# WIFI_ESP8285_ESP8266.net
KiCad netlist of a schematic drawn in Altium Designer
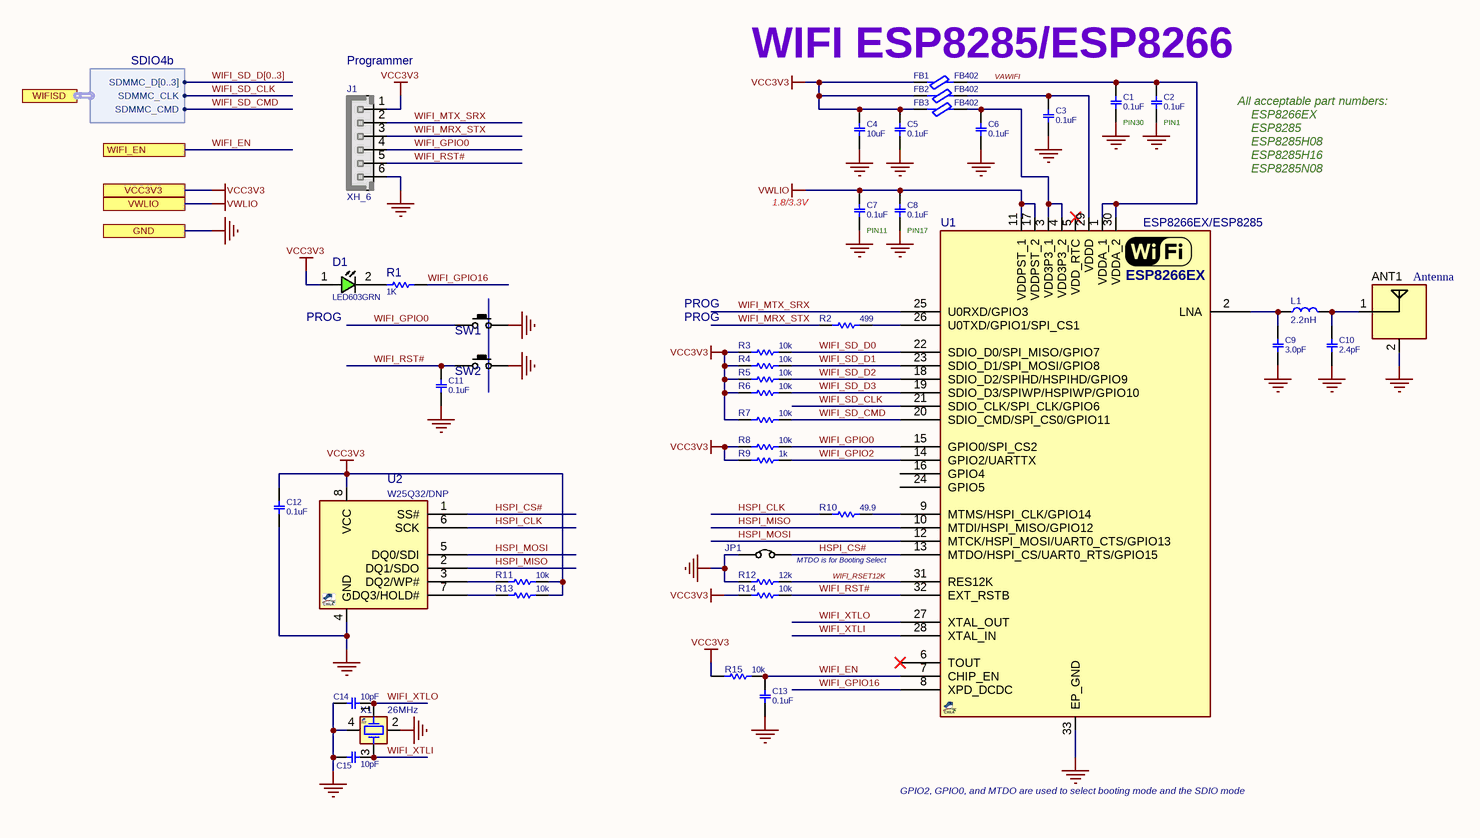
[diagram p0: WIFI_ESP8285_ESP8266.SchDoc]

(export (version "E")
  (design (tool "Eeschema 10.0.6"))
  (components
    (comp (ref "ANT1")
      (value "Antenna")
      (footprint "ANT_PCB_2P4G_IFA")
      (description "Antenna,Microstrip, 2.4GHz")
      (fields (field (name "MANF") "MANF") (field (name "MANF_P#") "MANF_P#"))
      (libsource (lib "antenna") (part "ANT_PCB_2P4G_IFA"))
    )
    (comp (ref "C1")
      (value "0.1uF")
      (footprint "C0402")
      (description "CAP, MLCC")
      (libsource (lib "mlcc_smd_passive") (part "CAP_SMD_MLCC_100n50T"))
    )
    (comp (ref "C2")
      (value "0.1uF")
      (footprint "C0402")
      (description "CAP, MLCC")
      (libsource (lib "mlcc_smd_passive") (part "CAP_SMD_MLCC_100n50T"))
    )
    (comp (ref "C3")
      (value "0.1uF")
      (footprint "C0402")
      (description "CAP, MLCC")
      (libsource (lib "mlcc_smd_passive") (part "CAP_SMD_MLCC_100n50T"))
    )
    (comp (ref "C4")
      (value "10uF")
      (footprint "C0402")
      (description "CAP, MLCC")
      (libsource (lib "mlcc_smd_passive") (part "CAP_SMD_MLCC_100n50T"))
    )
    (comp (ref "C5")
      (value "0.1uF")
      (footprint "C0402")
      (description "CAP, MLCC")
      (libsource (lib "mlcc_smd_passive") (part "CAP_SMD_MLCC_100n50T"))
    )
    (comp (ref "C6")
      (value "0.1uF")
      (footprint "C0402")
      (description "CAP, MLCC")
      (libsource (lib "mlcc_smd_passive") (part "CAP_SMD_MLCC_100n50T"))
    )
    (comp (ref "C7")
      (value "0.1uF")
      (footprint "C0402")
      (description "CAP, MLCC")
      (libsource (lib "mlcc_smd_passive") (part "CAP_SMD_MLCC_100n50T"))
    )
    (comp (ref "C8")
      (value "0.1uF")
      (footprint "C0402")
      (description "CAP, MLCC")
      (libsource (lib "mlcc_smd_passive") (part "CAP_SMD_MLCC_100n50T"))
    )
    (comp (ref "C9")
      (value "3.0pF")
      (footprint "C0402")
      (description "CAP, MLCC")
      (libsource (lib "mlcc_smd_passive") (part "CAP_SMD_MLCC_100n50T"))
    )
    (comp (ref "C10")
      (value "2.4pF")
      (footprint "C0402")
      (description "CAP, MLCC")
      (libsource (lib "mlcc_smd_passive") (part "CAP_SMD_MLCC_100n50T"))
    )
    (comp (ref "C11")
      (value "0.1uF")
      (footprint "C0402")
      (description "CAP, 100nF, 6.3V, C0G,  0402")
      (fields (field (name "MANF_P#") "MANF_PART#") (field (name "MANF") "Murata"))
      (libsource (lib "espwroom2_wifi_module") (part "CAP_SMD_MLCC_1"))
    )
    (comp (ref "C12")
      (value "0.1uF")
      (footprint "C0402")
      (description "CAP, MLCC")
      (libsource (lib "mlcc_smd_passive") (part "CAP_SMD_MLCC_100n50T"))
    )
    (comp (ref "C13")
      (value "0.1uF")
      (footprint "C0402")
      (description "CAP, MLCC")
      (libsource (lib "mlcc_smd_passive") (part "CAP_SMD_MLCC_100n50T"))
    )
    (comp (ref "C14")
      (value "10pF")
      (footprint "C0402")
      (description "CAP, 100nF, 6.3V, C0G,  0402")
      (fields (field (name "MANF_P#") "MANF_PART#") (field (name "MANF") "Murata"))
      (libsource (lib "espwroom2_wifi_module") (part "CAP_SMD_MLCC_1"))
    )
    (comp (ref "C15")
      (value "10pF")
      (footprint "C0402")
      (description "CAP, 100nF, 6.3V, C0G,  0402")
      (fields (field (name "MANF_P#") "MANF_PART#") (field (name "MANF") "Murata"))
      (libsource (lib "espwroom2_wifi_module") (part "CAP_SMD_MLCC_1"))
    )
    (comp (ref "D1")
      (value "LED603GRN")
      (footprint "LED0603")
      (description "LED, SMD, 0603, GREEN")
      (fields (field (name "MANF") "Kingbright") (field (name "MANF_P#") "APT1608SGC"))
      (libsource (lib "led(diode)") (part "LED_SMD_0603_GRN"))
    )
    (comp (ref "FB1")
      (value "FB402")
      (footprint "L0402")
      (description "FERRITE_Bead, 0402, 0.5A, 200mOhm, 120@100MHz")
      (fields (field (name "MANF") "MURATA") (field (name "MANF_P#") "BLM15AG121SN1D"))
      (libsource (lib "emi_filter") (part "FBEAD_SMD_BLM15PD121"))
    )
    (comp (ref "FB2")
      (value "FB402")
      (footprint "L0402")
      (description "FERRITE_Bead, 0402, 0.5A, 200mOhm, 120@100MHz")
      (fields (field (name "MANF") "MURATA") (field (name "MANF_P#") "BLM15AG121SN1D"))
      (libsource (lib "emi_filter") (part "FBEAD_SMD_BLM15PD121"))
    )
    (comp (ref "FB3")
      (value "FB402")
      (footprint "L0402")
      (description "FERRITE_Bead, 0402, 0.5A, 200mOhm, 120@100MHz")
      (fields (field (name "MANF") "MURATA") (field (name "MANF_P#") "BLM15AG121SN1D"))
      (libsource (lib "emi_filter") (part "FBEAD_SMD_BLM15PD121"))
    )
    (comp (ref "J1")
      (value "XH_6")
      (footprint "XH_6")
      (description "JST-XH pitch: 2.5mm")
      (fields (field (name "MANF_P#") "JST-S6B-XHA") (field (name "MANF") "JST"))
      (libsource (lib "conn_wire2board") (part "XH_6"))
    )
    (comp (ref "JP1")
      (value "JMPHDR2PIN")
      (footprint "JP_2_BLK")
      (description "JUMPER, HEADER 2PIN")
      (fields (field (name "MANF") "MANF") (field (name "MANF_P#") "MANF_P#"))
      (libsource (lib "test-tp_jumper") (part "JUMPER_HDR_2P"))
    )
    (comp (ref "L1")
      (value "2.2nH")
      (footprint "L0402")
      (description "INDUCTOR, SMD")
      (libsource (lib "passive_smd") (part "IND_SMD"))
    )
    (comp (ref "R1")
      (value "1K")
      (footprint "R0402")
      (description "RESISTOR, SMD")
      (fields (field (name "MANF_P#") "RK73H1ETTP4701F") (field (name "MANF") "KOA SPEER"))
      (libsource (lib "espwroom2_wifi_module") (part "RES_SMD"))
    )
    (comp (ref "R2")
      (value "499")
      (footprint "R0402")
      (description "RESISTOR, SMD")
      (libsource (lib "passive_res_smd") (part "RES_SMD_10K_0402"))
    )
    (comp (ref "R3")
      (value "10k")
      (footprint "R0402")
      (description "RESISTOR, SMD")
      (libsource (lib "passive_res_smd") (part "RES_SMD_10K_0402"))
    )
    (comp (ref "R4")
      (value "10k")
      (footprint "R0402")
      (description "RESISTOR, SMD")
      (libsource (lib "passive_res_smd") (part "RES_SMD_10K_0402"))
    )
    (comp (ref "R5")
      (value "10k")
      (footprint "R0402")
      (description "RESISTOR, SMD")
      (libsource (lib "passive_res_smd") (part "RES_SMD_10K_0402"))
    )
    (comp (ref "R6")
      (value "10k")
      (footprint "R0402")
      (description "RESISTOR, SMD")
      (libsource (lib "passive_res_smd") (part "RES_SMD_10K_0402"))
    )
    (comp (ref "R7")
      (value "10k")
      (footprint "R0402")
      (description "RESISTOR, SMD")
      (libsource (lib "passive_res_smd") (part "RES_SMD_10K_0402"))
    )
    (comp (ref "R8")
      (value "10k")
      (footprint "R0402")
      (description "RESISTOR, SMD")
      (libsource (lib "passive_res_smd") (part "RES_SMD_10K_0402"))
    )
    (comp (ref "R9")
      (value "1k")
      (footprint "R0402")
      (description "RESISTOR, SMD")
      (libsource (lib "passive_res_smd") (part "RES_SMD_10K_0402"))
    )
    (comp (ref "R10")
      (value "49.9")
      (footprint "R0402")
      (description "RESISTOR, SMD")
      (libsource (lib "passive_res_smd") (part "RES_SMD_10K_0402"))
    )
    (comp (ref "R11")
      (value "10k")
      (footprint "R0402")
      (description "RESISTOR, SMD")
      (libsource (lib "passive_res_smd") (part "RES_SMD_10K_0402"))
    )
    (comp (ref "R12")
      (value "12k")
      (footprint "R0402")
      (description "RESISTOR, SMD")
      (libsource (lib "passive_res_smd") (part "RES_SMD_10K_0402"))
    )
    (comp (ref "R13")
      (value "10k")
      (footprint "R0402")
      (description "RESISTOR, SMD")
      (libsource (lib "passive_res_smd") (part "RES_SMD_10K_0402"))
    )
    (comp (ref "R14")
      (value "10k")
      (footprint "R0402")
      (description "RESISTOR, SMD")
      (libsource (lib "passive_res_smd") (part "RES_SMD_10K_0402"))
    )
    (comp (ref "R15")
      (value "10k")
      (footprint "R0402")
      (description "RESISTOR, SMD")
      (libsource (lib "passive_res_smd") (part "RES_SMD_10K_0402"))
    )
    (comp (ref "SW1")
      (value "PUSHBUTTON")
      (footprint "SWPBS_SPST_3X2X1")
      (description "SWITCH, PUSH BUTTON, TACTILE, SMD, SPST, 3X2.5X1.2mm")
      (fields (field (name "MANF") "OMRON") (field (name "MANF_P#") "B3U-1000P"))
      (libsource (lib "switch_tact_PUSHB") (part "SWPBS_SPST_3X2_B3U-1000P"))
    )
    (comp (ref "SW2")
      (value "PUSHBUTTON")
      (footprint "SWPBS_SPST_3X2X1")
      (description "SWITCH, PUSH BUTTON, TACTILE, SMD, SPST, 3X2.5X1.2mm")
      (fields (field (name "MANF") "OMRON") (field (name "MANF_P#") "B3U-1000P"))
      (libsource (lib "switch_tact_PUSHB") (part "SWPBS_SPST_3X2_B3U-1000P"))
    )
    (comp (ref "U1")
      (value "ESP8266EX/ESP8285")
      (footprint "QFN50_32T")
      (description "ESP8266EX, RF SoC")
      (fields (field (name "MANF") "Espressif Systems") (field (name "MANF_P#") "ESP8266EX"))
      (libsource (lib "wifi_ic") (part "ESP8266EX_QFN32"))
    )
    (comp (ref "U2")
      (value "W25Q32/DNP")
      (footprint "SO_8_W")
      (description "SPI FLASH Memory, 64Mb (8M x8), 104MHz")
      (fields (field (name "MANF") "WINBOND") (field (name "MANF_P#") "W25Q32JVSSIQ"))
      (libsource (lib "memory_flash_spi") (part "W25Q64FV_SO8W"))
    )
    (comp (ref "X1")
      (value "26MHz")
      (footprint "XTL_4_2016")
      (description "Crystal 26MHz")
      (fields (field (name "MANF") "MURATA") (field (name "MANF_P#") "XRCGB26M000F1H00R0"))
      (libsource (lib "crystal") (part "XTL_4_26MHz_2016"))
    )
  )
  (nets
    (net (code "2") (name "/HSPI_CLK") (class "Default")
      (node (ref "R10") (pin "1") (pinfunction "1_1") (pintype "passive"))
      (node (ref "U2") (pin "6") (pinfunction "SCK_6") (pintype "passive"))
    )
    (net (code "3") (name "/HSPI_CS#") (class "Default")
      (node (ref "JP1") (pin "2") (pinfunction "2_2") (pintype "passive"))
      (node (ref "U1") (pin "13") (pinfunction "MTDO/HSPI_CS/UART0_RTS/GPIO15_13") (pintype "passive"))
      (node (ref "U2") (pin "1") (pinfunction "SS#_1") (pintype "passive"))
    )
    (net (code "4") (name "/HSPI_MISO") (class "Default")
      (node (ref "U1") (pin "10") (pinfunction "MTDI/HSPI_MISO/GPIO12_10") (pintype "passive"))
      (node (ref "U2") (pin "2") (pinfunction "DQ1/SDO_2") (pintype "passive"))
    )
    (net (code "5") (name "/HSPI_MOSI") (class "Default")
      (node (ref "U1") (pin "12") (pinfunction "MTCK/HSPI_MOSI/UART0_CTS/GPIO13_12") (pintype "passive"))
      (node (ref "U2") (pin "5") (pinfunction "DQ0/SDI_5") (pintype "passive"))
    )
    (net (code "6") (name "/VAWIFI") (class "Default")
      (node (ref "C1") (pin "1") (pinfunction "1_1") (pintype "passive"))
      (node (ref "C2") (pin "1") (pinfunction "1_1") (pintype "passive"))
      (node (ref "FB1") (pin "2") (pinfunction "2_2") (pintype "passive"))
      (node (ref "U1") (pin "1") (pinfunction "VDDA_1_1") (pintype "passive"))
      (node (ref "U1") (pin "30") (pinfunction "VDDA_2_30") (pintype "passive"))
    )
    (net (code "8") (name "/WIFI_EN") (class "Default")
      (node (ref "C13") (pin "1") (pinfunction "1_1") (pintype "passive"))
      (node (ref "R15") (pin "2") (pinfunction "2_2") (pintype "passive"))
      (node (ref "U1") (pin "7") (pinfunction "CHIP_EN_7") (pintype "passive"))
    )
    (net (code "9") (name "/WIFI_GPIO0") (class "Default")
      (node (ref "J1") (pin "4") (pinfunction "4_4") (pintype "passive"))
      (node (ref "R8") (pin "2") (pinfunction "2_2") (pintype "passive"))
      (node (ref "SW1") (pin "1") (pinfunction "P1_1") (pintype "passive"))
      (node (ref "U1") (pin "15") (pinfunction "GPIO0/SPI_CS2_15") (pintype "passive"))
    )
    (net (code "10") (name "/WIFI_GPIO2") (class "Default")
      (node (ref "R9") (pin "2") (pinfunction "2_2") (pintype "passive"))
      (node (ref "U1") (pin "14") (pinfunction "GPIO2/UARTTX_14") (pintype "passive"))
    )
    (net (code "11") (name "/WIFI_GPIO16") (class "Default")
      (node (ref "R1") (pin "2") (pinfunction "2_2") (pintype "passive"))
      (node (ref "U1") (pin "8") (pinfunction "XPD_DCDC_8") (pintype "passive"))
    )
    (net (code "12") (name "/WIFI_MRX_STX") (class "Default")
      (node (ref "J1") (pin "3") (pinfunction "3_3") (pintype "passive"))
      (node (ref "R2") (pin "1") (pinfunction "1_1") (pintype "passive"))
    )
    (net (code "13") (name "/WIFI_MTX_SRX") (class "Default")
      (node (ref "J1") (pin "2") (pinfunction "2_2") (pintype "passive"))
      (node (ref "U1") (pin "25") (pinfunction "U0RXD/GPIO3_25") (pintype "passive"))
    )
    (net (code "14") (name "/WIFI_RSET12K") (class "Default")
      (node (ref "R12") (pin "2") (pinfunction "2_2") (pintype "passive"))
      (node (ref "U1") (pin "31") (pinfunction "RES12K_31") (pintype "passive"))
    )
    (net (code "15") (name "/WIFI_RST#") (class "Default")
      (node (ref "C11") (pin "2") (pinfunction "2_2") (pintype "passive"))
      (node (ref "J1") (pin "5") (pinfunction "5_5") (pintype "passive"))
      (node (ref "R14") (pin "2") (pinfunction "2_2") (pintype "passive"))
      (node (ref "SW2") (pin "1") (pinfunction "P1_1") (pintype "passive"))
      (node (ref "U1") (pin "32") (pinfunction "EXT_RSTB_32") (pintype "passive"))
    )
    (net (code "16") (name "/WIFI_SD_CLK") (class "Default")
      (node (ref "U1") (pin "21") (pinfunction "SDIO_CLK/SPI_CLK/GPIO6_21") (pintype "passive"))
    )
    (net (code "17") (name "/WIFI_SD_CMD") (class "Default")
      (node (ref "R7") (pin "2") (pinfunction "2_2") (pintype "passive"))
      (node (ref "U1") (pin "20") (pinfunction "SDIO_CMD/SPI_CS0/GPIO11_20") (pintype "passive"))
    )
    (net (code "18") (name "/WIFI_SD_D0") (class "Default")
      (node (ref "R3") (pin "2") (pinfunction "2_2") (pintype "passive"))
      (node (ref "U1") (pin "22") (pinfunction "SDIO_D0/SPI_MISO/GPIO7_22") (pintype "passive"))
    )
    (net (code "19") (name "/WIFI_SD_D1") (class "Default")
      (node (ref "R4") (pin "2") (pinfunction "2_2") (pintype "passive"))
      (node (ref "U1") (pin "23") (pinfunction "SDIO_D1/SPI_MOSI/GPIO8_23") (pintype "passive"))
    )
    (net (code "20") (name "/WIFI_SD_D2") (class "Default")
      (node (ref "R5") (pin "2") (pinfunction "2_2") (pintype "passive"))
      (node (ref "U1") (pin "18") (pinfunction "SDIO_D2/SPIHD/HSPIHD/GPIO9_18") (pintype "passive"))
    )
    (net (code "21") (name "/WIFI_SD_D3") (class "Default")
      (node (ref "R6") (pin "2") (pinfunction "2_2") (pintype "passive"))
      (node (ref "U1") (pin "19") (pinfunction "SDIO_D3/SPIWP/HSPIWP/GPIO10_19") (pintype "passive"))
    )
    (net (code "22") (name "/WIFI_XTLI") (class "Default")
      (node (ref "C15") (pin "2") (pinfunction "2_2") (pintype "passive"))
      (node (ref "U1") (pin "28") (pinfunction "XTAL_IN_28") (pintype "passive"))
      (node (ref "X1") (pin "3") (pinfunction "2_3") (pintype "passive"))
    )
    (net (code "23") (name "/WIFI_XTLO") (class "Default")
      (node (ref "C14") (pin "2") (pinfunction "2_2") (pintype "passive"))
      (node (ref "U1") (pin "27") (pinfunction "XTAL_OUT_27") (pintype "passive"))
      (node (ref "X1") (pin "1") (pinfunction "1_1") (pintype "passive"))
    )
    (net (code "25") (name "GND") (class "Default")
      (node (ref "ANT1") (pin "2") (pinfunction "RETURN_2") (pintype "passive"))
      (node (ref "C1") (pin "2") (pinfunction "2_2") (pintype "passive"))
      (node (ref "C10") (pin "1") (pinfunction "1_1") (pintype "passive"))
      (node (ref "C11") (pin "1") (pinfunction "1_1") (pintype "passive"))
      (node (ref "C12") (pin "2") (pinfunction "2_2") (pintype "passive"))
      (node (ref "C13") (pin "2") (pinfunction "2_2") (pintype "passive"))
      (node (ref "C14") (pin "1") (pinfunction "1_1") (pintype "passive"))
      (node (ref "C15") (pin "1") (pinfunction "1_1") (pintype "passive"))
      (node (ref "C2") (pin "2") (pinfunction "2_2") (pintype "passive"))
      (node (ref "C3") (pin "2") (pinfunction "2_2") (pintype "passive"))
      (node (ref "C4") (pin "1") (pinfunction "1_1") (pintype "passive"))
      (node (ref "C5") (pin "1") (pinfunction "1_1") (pintype "passive"))
      (node (ref "C6") (pin "2") (pinfunction "2_2") (pintype "passive"))
      (node (ref "C7") (pin "2") (pinfunction "2_2") (pintype "passive"))
      (node (ref "C8") (pin "2") (pinfunction "2_2") (pintype "passive"))
      (node (ref "C9") (pin "1") (pinfunction "1_1") (pintype "passive"))
      (node (ref "J1") (pin "6") (pinfunction "6_6") (pintype "passive"))
      (node (ref "JP1") (pin "1") (pinfunction "1_1") (pintype "passive"))
      (node (ref "R12") (pin "1") (pinfunction "1_1") (pintype "passive"))
      (node (ref "SW1") (pin "2") (pinfunction "P3_2") (pintype "passive"))
      (node (ref "SW2") (pin "2") (pinfunction "P3_2") (pintype "passive"))
      (node (ref "U1") (pin "33") (pinfunction "EP_GND_33") (pintype "passive"))
      (node (ref "U2") (pin "4") (pinfunction "GND_4") (pintype "passive"))
      (node (ref "X1") (pin "2") (pinfunction "2_2") (pintype "passive"))
      (node (ref "X1") (pin "4") (pinfunction "4_4") (pintype "passive"))
    )
    (net (code "26") (name "Net-(ANT1-FEEDER)") (class "Default")
      (node (ref "ANT1") (pin "1") (pinfunction "FEEDER_1") (pintype "passive"))
      (node (ref "C10") (pin "2") (pinfunction "2_2") (pintype "passive"))
      (node (ref "L1") (pin "1") (pinfunction "1_1") (pintype "passive"))
    )
    (net (code "27") (name "Net-(D1-CATHODE)") (class "Default")
      (node (ref "D1") (pin "2") (pinfunction "CATHODE_2") (pintype "passive"))
      (node (ref "R1") (pin "1") (pinfunction "1_1") (pintype "passive"))
    )
    (net (code "28") (name "Net-(U1-LNA)") (class "Default")
      (node (ref "C9") (pin "2") (pinfunction "2_2") (pintype "passive"))
      (node (ref "L1") (pin "2") (pinfunction "2_2") (pintype "passive"))
      (node (ref "U1") (pin "2") (pinfunction "LNA_2") (pintype "passive"))
    )
    (net (code "29") (name "Net-(U1-MTMS{slash}HSPI_CLK{slash}GPIO14)") (class "Default")
      (node (ref "R10") (pin "2") (pinfunction "2_2") (pintype "passive"))
      (node (ref "U1") (pin "9") (pinfunction "MTMS/HSPI_CLK/GPIO14_9") (pintype "passive"))
    )
    (net (code "30") (name "Net-(U1-U0TXD{slash}GPIO1{slash}SPI_CS1)") (class "Default")
      (node (ref "R2") (pin "2") (pinfunction "2_2") (pintype "passive"))
      (node (ref "U1") (pin "26") (pinfunction "U0TXD/GPIO1/SPI_CS1_26") (pintype "passive"))
    )
    (net (code "31") (name "Net-(U1-VDD3P3_1)") (class "Default")
      (node (ref "C6") (pin "1") (pinfunction "1_1") (pintype "passive"))
      (node (ref "FB3") (pin "1") (pinfunction "1_1") (pintype "passive"))
      (node (ref "U1") (pin "3") (pinfunction "VDD3P3_1_3") (pintype "passive"))
      (node (ref "U1") (pin "4") (pinfunction "VDD3P3_2_4") (pintype "passive"))
    )
    (net (code "32") (name "Net-(U1-VDDD)") (class "Default")
      (node (ref "C3") (pin "1") (pinfunction "1_1") (pintype "passive"))
      (node (ref "FB2") (pin "1") (pinfunction "1_1") (pintype "passive"))
      (node (ref "U1") (pin "29") (pinfunction "VDDD_29") (pintype "passive"))
    )
    (net (code "33") (name "Net-(U2-DQ2{slash}WP#)") (class "Default")
      (node (ref "R11") (pin "1") (pinfunction "1_1") (pintype "passive"))
      (node (ref "U2") (pin "3") (pinfunction "DQ2/WP#_3") (pintype "passive"))
    )
    (net (code "34") (name "Net-(U2-DQ3{slash}HOLD#)") (class "Default")
      (node (ref "R13") (pin "1") (pinfunction "1_1") (pintype "passive"))
      (node (ref "U2") (pin "7") (pinfunction "DQ3/HOLD#_7") (pintype "passive"))
    )
    (net (code "35") (name "VCC3V3") (class "Default")
      (node (ref "C12") (pin "1") (pinfunction "1_1") (pintype "passive"))
      (node (ref "C4") (pin "2") (pinfunction "2_2") (pintype "passive"))
      (node (ref "C5") (pin "2") (pinfunction "2_2") (pintype "passive"))
      (node (ref "D1") (pin "1") (pinfunction "ANODE_1") (pintype "passive"))
      (node (ref "FB1") (pin "1") (pinfunction "1_1") (pintype "passive"))
      (node (ref "FB2") (pin "2") (pinfunction "2_2") (pintype "passive"))
      (node (ref "FB3") (pin "2") (pinfunction "2_2") (pintype "passive"))
      (node (ref "J1") (pin "1") (pinfunction "1_1") (pintype "passive"))
      (node (ref "R11") (pin "2") (pinfunction "2_2") (pintype "passive"))
      (node (ref "R13") (pin "2") (pinfunction "2_2") (pintype "passive"))
      (node (ref "R14") (pin "1") (pinfunction "1_1") (pintype "passive"))
      (node (ref "R15") (pin "1") (pinfunction "1_1") (pintype "passive"))
      (node (ref "R3") (pin "1") (pinfunction "1_1") (pintype "passive"))
      (node (ref "R4") (pin "1") (pinfunction "1_1") (pintype "passive"))
      (node (ref "R5") (pin "1") (pinfunction "1_1") (pintype "passive"))
      (node (ref "R6") (pin "1") (pinfunction "1_1") (pintype "passive"))
      (node (ref "R7") (pin "1") (pinfunction "1_1") (pintype "passive"))
      (node (ref "R8") (pin "1") (pinfunction "1_1") (pintype "passive"))
      (node (ref "R9") (pin "1") (pinfunction "1_1") (pintype "passive"))
      (node (ref "U2") (pin "8") (pinfunction "VCC_8") (pintype "passive"))
    )
    (net (code "36") (name "VWLIO") (class "Default")
      (node (ref "C7") (pin "1") (pinfunction "1_1") (pintype "passive"))
      (node (ref "C8") (pin "1") (pinfunction "1_1") (pintype "passive"))
      (node (ref "U1") (pin "11") (pinfunction "VDDPST_1_11") (pintype "passive"))
      (node (ref "U1") (pin "17") (pinfunction "VDDPST_2_17") (pintype "passive"))
    )
    (net (code "37") (name "unconnected-(U1-GPIO4-Pad16)") (class "Default")
      (node (ref "U1") (pin "16") (pinfunction "GPIO4_16") (pintype "passive"))
    )
    (net (code "38") (name "unconnected-(U1-GPIO5-Pad24)") (class "Default")
      (node (ref "U1") (pin "24") (pinfunction "GPIO5_24") (pintype "passive"))
    )
    (net (code "39") (name "unconnected-(U1-TOUT-Pad6)") (class "Default")
      (node (ref "U1") (pin "6") (pinfunction "TOUT_6") (pintype "passive+no_connect"))
    )
    (net (code "40") (name "unconnected-(U1-VDD_RTC-Pad5)") (class "Default")
      (node (ref "U1") (pin "5") (pinfunction "VDD_RTC_5") (pintype "passive+no_connect"))
    )
  )
)
